# KeeWatch_SAMD21.net
KiCad netlist of a schematic drawn in Altium Designer
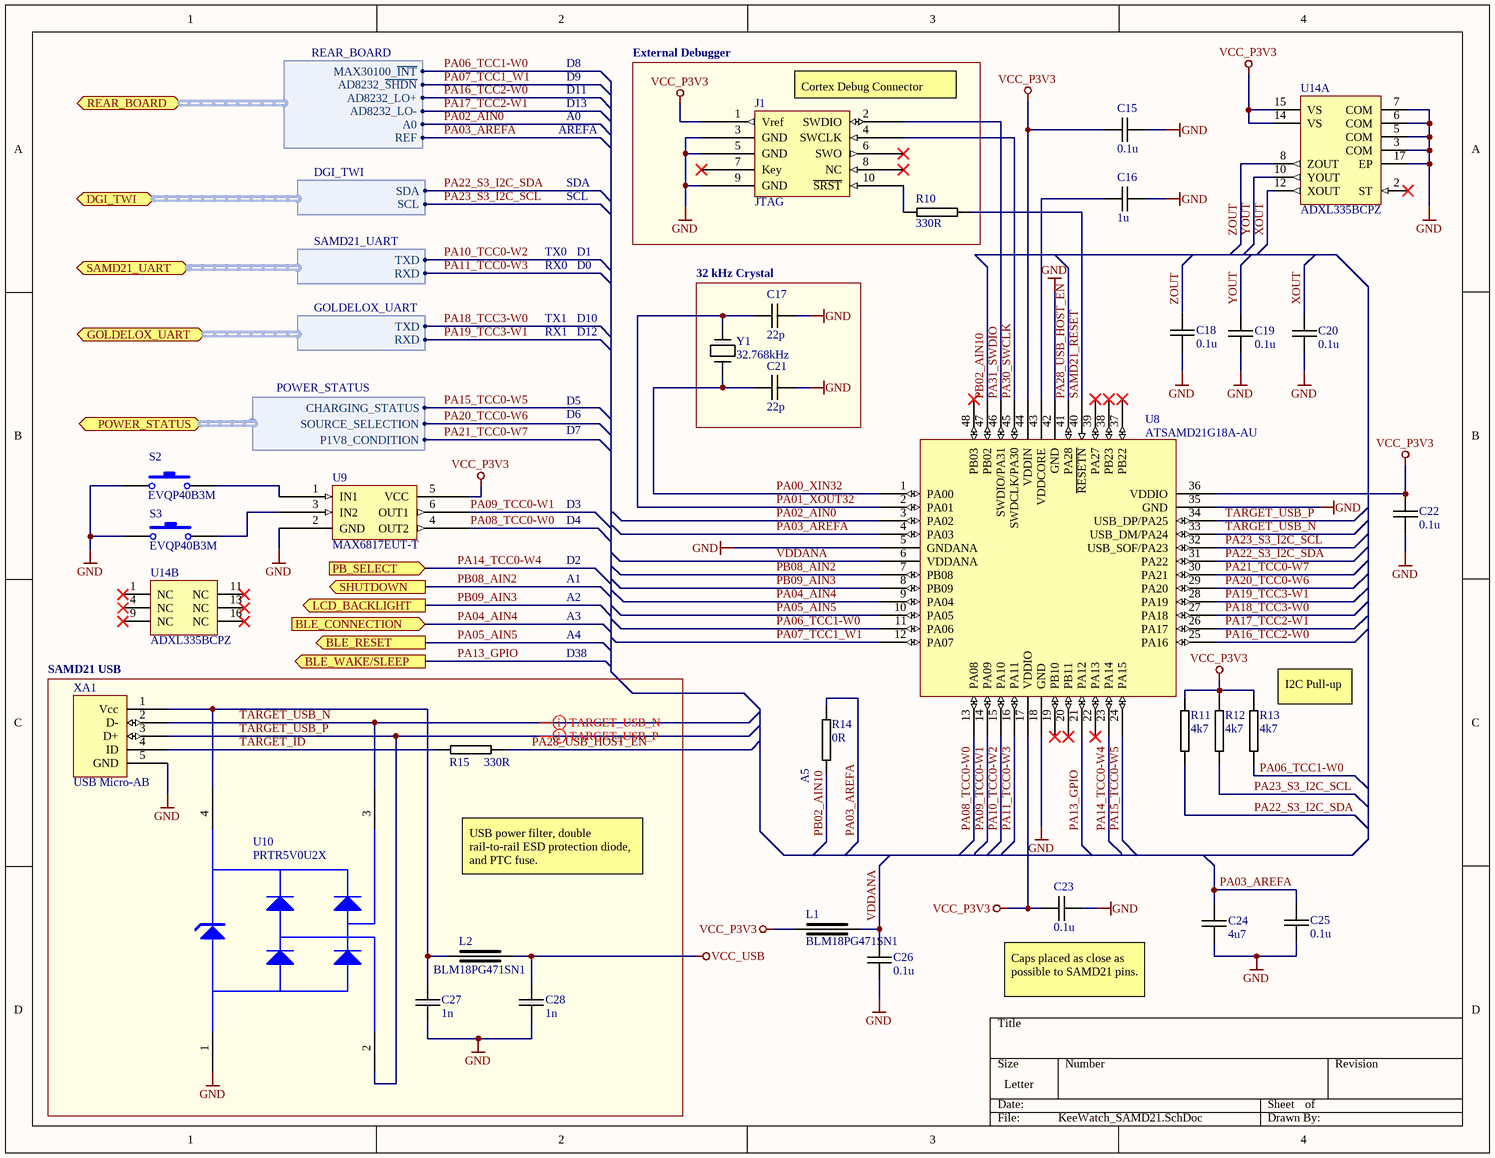
[diagram p0: KeeWatch_SAMD21.SchDoc]

(export (version "E")
  (design (tool "Eeschema 10.0.6"))
  (components
    (comp (ref "C15")
      (value "0.1u")
      (footprint "0603-Cap")
      (description "CAPACITOR 0603 CERAMIC")
      (libsource (lib "Passives") (part "0603-Cap"))
    )
    (comp (ref "C16")
      (value "1u")
      (footprint "0603-Cap")
      (description "CAPACITOR 0603 CERAMIC")
      (libsource (lib "Passives") (part "0603-Cap"))
    )
    (comp (ref "C17")
      (value "22p")
      (footprint "0603-Cap")
      (description "CAPACITOR 0603 CERAMIC")
      (libsource (lib "Passives") (part "0603-Cap"))
    )
    (comp (ref "C18")
      (value "0.1u")
      (footprint "0603-Cap")
      (description "CAPACITOR 0603 CERAMIC")
      (libsource (lib "Passives") (part "0603-Cap"))
    )
    (comp (ref "C19")
      (value "0.1u")
      (footprint "0603-Cap")
      (description "CAPACITOR 0603 CERAMIC")
      (libsource (lib "Passives") (part "0603-Cap"))
    )
    (comp (ref "C20")
      (value "0.1u")
      (footprint "0603-Cap")
      (description "CAPACITOR 0603 CERAMIC")
      (libsource (lib "Passives") (part "0603-Cap"))
    )
    (comp (ref "C21")
      (value "22p")
      (footprint "0603-Cap")
      (description "CAPACITOR 0603 CERAMIC")
      (libsource (lib "Passives") (part "0603-Cap"))
    )
    (comp (ref "C22")
      (value "0.1u")
      (footprint "0603-Cap")
      (description "CAPACITOR 0603 CERAMIC")
      (libsource (lib "Passives") (part "0603-Cap"))
    )
    (comp (ref "C23")
      (value "0.1u")
      (footprint "0603-Cap")
      (description "CAPACITOR 0603 CERAMIC")
      (libsource (lib "Passives") (part "0603-Cap"))
    )
    (comp (ref "C24")
      (value "4u7")
      (footprint "0603-Cap")
      (description "CAPACITOR 0603 CERAMIC")
      (libsource (lib "Passives") (part "0603-Cap"))
    )
    (comp (ref "C25")
      (value "0.1u")
      (footprint "0603-Cap")
      (description "CAPACITOR 0603 CERAMIC")
      (libsource (lib "Passives") (part "0603-Cap"))
    )
    (comp (ref "C26")
      (value "0.1u")
      (footprint "0603-Cap")
      (description "CAPACITOR 0603 CERAMIC")
      (libsource (lib "Passives") (part "0603-Cap"))
    )
    (comp (ref "C27")
      (value "1n")
      (footprint "0603-Cap")
      (description "CAPACITOR 0603 CERAMIC")
      (libsource (lib "Passives") (part "0603-Cap"))
    )
    (comp (ref "C28")
      (value "1n")
      (footprint "0603-Cap")
      (description "CAPACITOR 0603 CERAMIC")
      (libsource (lib "Passives") (part "0603-Cap"))
    )
    (comp (ref "J1")
      (value "JTAG")
      (footprint "SWD CONNECTOR")
      (description "JTAG CONNECTOR")
      (libsource (lib "Schlib2") (part "JTAG"))
    )
    (comp (ref "L1")
      (value "BLM18PG471SN1")
      (footprint "0603-IND")
      (description "FERRITE BEAD 1000 OHM 400mA")
      (fields
        (field (name "MANUFACTURER") "TDK Corporation")
        (field (name "MANUFACTURER PART NUMBER") "MMZ1608R102A")
      )
      (libsource (lib "vh_altium_library") (part "0603FB-1KZ"))
    )
    (comp (ref "L2")
      (value "BLM18PG471SN1")
      (footprint "0603-IND")
      (description "FERRITE BEAD 1000 OHM 400mA")
      (fields
        (field (name "MANUFACTURER") "TDK Corporation")
        (field (name "MANUFACTURER PART NUMBER") "MMZ1608R102A")
      )
      (libsource (lib "vh_altium_library") (part "0603FB-1KZ"))
    )
    (comp (ref "R10")
      (value "330R")
      (footprint "0603-RES")
      (description "GENERIC RESISTOR 0603")
      (libsource (lib "Passives") (part "0603-Res"))
    )
    (comp (ref "R11")
      (value "4k7")
      (footprint "0603-RES")
      (description "GENERIC RESISTOR 0603")
      (libsource (lib "Passives") (part "0603-Res"))
    )
    (comp (ref "R12")
      (value "4k7")
      (footprint "0603-RES")
      (description "GENERIC RESISTOR 0603")
      (libsource (lib "Passives") (part "0603-Res"))
    )
    (comp (ref "R13")
      (value "4k7")
      (footprint "0603-RES")
      (description "GENERIC RESISTOR 0603")
      (libsource (lib "Passives") (part "0603-Res"))
    )
    (comp (ref "R14")
      (value "0R")
      (footprint "0603-RES")
      (description "GENERIC RESISTOR 0603")
      (libsource (lib "Passives") (part "0603-Res"))
    )
    (comp (ref "R15")
      (value "330R")
      (footprint "0603-RES")
      (description "GENERIC RESISTOR 0603")
      (libsource (lib "Passives") (part "0603-Res"))
    )
    (comp (ref "S2") (value "EVQP40B3M") (footprint "EVQP4") (libsource (lib "WATCH") (part "EVQP40B3M")))
    (comp (ref "S3") (value "EVQP40B3M") (footprint "EVQP4") (libsource (lib "WATCH") (part "EVQP40B3M")))
    (comp (ref "U8")
      (value "ATSAMD21G18A-AU")
      (footprint "WATCH:48AA_N")
      (libsource (lib "WATCH") (part "ATSAMD21G18A-AU"))
    )
    (comp (ref "U9")
      (value "MAX6817EUT-T")
      (footprint "WATCH:Z6+1_N")
      (description "±15kV ESD-Protected,Dual, CMOS Switch Debouncer")
      (libsource (lib "Schlib2") (part "MAX6817EUT-T"))
    )
    (comp (ref "U10")
      (value "PRTR5V0U2X")
      (footprint "SOT143B")
      (libsource (lib "WATCH") (part "PRTR5V0U2X"))
    )
    (comp (ref "U14")
      (value "ADXL335BCPZ")
      (footprint "WATCH:ADI-CP-16-14_N")
      (fields (field (name "MANUFACTURER") "Analog Devices"))
      (libsource (lib "") (part "ADXL335BCPZ_1"))
    )
    (comp (ref "XA1")
      (value "USB Micro-AB")
      (footprint "MICRO USB B")
      (description "USB Connectors MICRO USB B RECEPT TOP MOUNT")
      (libsource (lib "WATCH") (part "MICRO USB B"))
    )
    (comp (ref "Y1")
      (value "32.768kHz")
      (footprint "32.768KHZ CRYSTAL")
      (description "32.768kHz SMD LOW PROFILE CRYSTAL")
      (libsource (lib "WATCH") (part "ABS05-32.768KHZ-9-T"))
    )
  )
  (nets
    (net (code "6") (name "/PA00_XIN32") (class "Default")
      (node (ref "C21") (pin "1") (pintype "passive"))
      (node (ref "U8") (pin "1") (pinfunction "PA00_1") (pintype "bidirectional"))
      (node (ref "Y1") (pin "1") (pintype "passive"))
    )
    (net (code "7") (name "/PA01_XOUT32") (class "Default")
      (node (ref "C17") (pin "1") (pintype "passive"))
      (node (ref "U8") (pin "2") (pinfunction "PA01_2") (pintype "bidirectional"))
      (node (ref "Y1") (pin "2") (pintype "passive"))
    )
    (net (code "8") (name "/PA02_AIN0") (class "Default")
      (node (ref "U8") (pin "3") (pinfunction "PA02_3") (pintype "bidirectional"))
    )
    (net (code "9") (name "/PA03_AREFA") (class "Default")
      (node (ref "C24") (pin "2") (pintype "passive"))
      (node (ref "C25") (pin "2") (pintype "passive"))
      (node (ref "R14") (pin "1") (pintype "passive"))
      (node (ref "U8") (pin "4") (pinfunction "PA03_4") (pintype "bidirectional"))
    )
    (net (code "10") (name "/PA04_AIN4") (class "Default")
      (node (ref "U8") (pin "9") (pinfunction "PA04_9") (pintype "bidirectional"))
    )
    (net (code "11") (name "/PA05_AIN5") (class "Default")
      (node (ref "U8") (pin "10") (pinfunction "PA05_10") (pintype "bidirectional"))
    )
    (net (code "12") (name "/PA06_TCC1-W0") (class "Default")
      (node (ref "R13") (pin "2") (pintype "passive"))
      (node (ref "U8") (pin "11") (pinfunction "PA06_11") (pintype "bidirectional"))
    )
    (net (code "13") (name "/PA07_TCC1_W1") (class "Default")
      (node (ref "U8") (pin "12") (pinfunction "PA07_12") (pintype "bidirectional"))
    )
    (net (code "14") (name "/PA08_TCC0-W0") (class "Default")
      (node (ref "U8") (pin "13") (pinfunction "PA08_13") (pintype "bidirectional"))
      (node (ref "U9") (pin "4") (pinfunction "OUT2_4") (pintype "output"))
    )
    (net (code "15") (name "/PA09_TCC0-W1") (class "Default")
      (node (ref "U8") (pin "14") (pinfunction "PA09_14") (pintype "bidirectional"))
      (node (ref "U9") (pin "6") (pinfunction "OUT1_6") (pintype "output"))
    )
    (net (code "16") (name "/PA10_TCC0-W2") (class "Default")
      (node (ref "U8") (pin "15") (pinfunction "PA10_15") (pintype "bidirectional"))
    )
    (net (code "17") (name "/PA11_TCC0-W3") (class "Default")
      (node (ref "U8") (pin "16") (pinfunction "PA11_16") (pintype "bidirectional"))
    )
    (net (code "18") (name "/PA13_GPIO") (class "Default")
      (node (ref "U8") (pin "21") (pinfunction "PA12_21") (pintype "bidirectional"))
    )
    (net (code "19") (name "/PA14_TCC0-W4") (class "Default")
      (node (ref "U8") (pin "23") (pinfunction "PA14_23") (pintype "bidirectional"))
    )
    (net (code "20") (name "/PA15_TCC0-W5") (class "Default")
      (node (ref "U8") (pin "24") (pinfunction "PA15_24") (pintype "bidirectional"))
    )
    (net (code "21") (name "/PA16_TCC2-W0") (class "Default")
      (node (ref "U8") (pin "25") (pinfunction "PA16_25") (pintype "bidirectional"))
    )
    (net (code "22") (name "/PA17_TCC2-W1") (class "Default")
      (node (ref "U8") (pin "26") (pinfunction "PA17_26") (pintype "bidirectional"))
    )
    (net (code "23") (name "/PA18_TCC3-W0") (class "Default")
      (node (ref "U8") (pin "27") (pinfunction "PA18_27") (pintype "bidirectional"))
    )
    (net (code "24") (name "/PA19_TCC3-W1") (class "Default")
      (node (ref "U8") (pin "28") (pinfunction "PA19_28") (pintype "bidirectional"))
    )
    (net (code "25") (name "/PA20_TCC0-W6") (class "Default")
      (node (ref "U8") (pin "29") (pinfunction "PA20_29") (pintype "bidirectional"))
    )
    (net (code "26") (name "/PA21_TCC0-W7") (class "Default")
      (node (ref "U8") (pin "30") (pinfunction "PA21_30") (pintype "bidirectional"))
    )
    (net (code "27") (name "/PA22_S3_I2C_SDA") (class "Default")
      (node (ref "R11") (pin "2") (pintype "passive"))
      (node (ref "U8") (pin "31") (pinfunction "PA22_31") (pintype "bidirectional"))
    )
    (net (code "28") (name "/PA23_S3_I2C_SCL") (class "Default")
      (node (ref "R12") (pin "2") (pintype "passive"))
      (node (ref "U8") (pin "32") (pinfunction "USB_SOF/PA23_32") (pintype "bidirectional"))
    )
    (net (code "29") (name "/PA28_USB_HOST_EN") (class "Default")
      (node (ref "R15") (pin "2") (pintype "passive"))
      (node (ref "U8") (pin "41") (pinfunction "PA28_41") (pintype "bidirectional"))
    )
    (net (code "30") (name "/PA30_SWCLK") (class "Default")
      (node (ref "J1") (pin "4") (pinfunction "SWCLK_4") (pintype "input"))
      (node (ref "U8") (pin "45") (pinfunction "SWDCLK/PA30_45") (pintype "bidirectional"))
    )
    (net (code "31") (name "/PA31_SWDIO") (class "Default")
      (node (ref "J1") (pin "2") (pinfunction "SWDIO_2") (pintype "bidirectional"))
      (node (ref "U8") (pin "46") (pinfunction "SWDIO/PA31_46") (pintype "bidirectional"))
    )
    (net (code "32") (name "/PB02_AIN10") (class "Default")
      (node (ref "R14") (pin "2") (pintype "passive"))
      (node (ref "U8") (pin "47") (pinfunction "PB02_47") (pintype "bidirectional"))
    )
    (net (code "33") (name "/PB08_AIN2") (class "Default")
      (node (ref "U8") (pin "7") (pinfunction "PB08_7") (pintype "bidirectional"))
    )
    (net (code "34") (name "/PB09_AIN3") (class "Default")
      (node (ref "U8") (pin "8") (pinfunction "PB09_8") (pintype "bidirectional"))
    )
    (net (code "35") (name "/SAMD21_RESET") (class "Default")
      (node (ref "R10") (pin "2") (pintype "passive"))
      (node (ref "U8") (pin "40") (pinfunction "~{RESETN}_40") (pintype "input"))
    )
    (net (code "36") (name "/TARGET_ID") (class "Default")
      (node (ref "R15") (pin "1") (pintype "passive"))
      (node (ref "XA1") (pin "4") (pinfunction "ID_4") (pintype "passive"))
    )
    (net (code "37") (name "/TARGET_USB_N") (class "Default")
      (node (ref "U10") (pin "3") (pinfunction "3_3") (pintype "passive"))
      (node (ref "U8") (pin "33") (pinfunction "USB_DM/PA24_33") (pintype "bidirectional"))
      (node (ref "XA1") (pin "2") (pinfunction "D-_2") (pintype "bidirectional"))
    )
    (net (code "38") (name "/TARGET_USB_P") (class "Default")
      (node (ref "U10") (pin "2") (pinfunction "2_2") (pintype "passive"))
      (node (ref "U8") (pin "34") (pinfunction "USB_DP/PA25_34") (pintype "bidirectional"))
      (node (ref "XA1") (pin "3") (pinfunction "D+_3") (pintype "bidirectional"))
    )
    (net (code "39") (name "/VDDANA") (class "Default")
      (node (ref "C26") (pin "1") (pintype "passive"))
      (node (ref "L1") (pin "1") (pintype "passive"))
      (node (ref "U8") (pin "6") (pinfunction "VDDANA_6") (pintype "power_in"))
    )
    (net (code "40") (name "/XOUT") (class "Default")
      (node (ref "C20") (pin "1") (pintype "passive"))
      (node (ref "U14") (pin "12") (pinfunction "XOUT_12") (pintype "output"))
    )
    (net (code "41") (name "/YOUT") (class "Default")
      (node (ref "C19") (pin "1") (pintype "passive"))
      (node (ref "U14") (pin "10") (pinfunction "YOUT_10") (pintype "output"))
    )
    (net (code "42") (name "/ZOUT") (class "Default")
      (node (ref "C18") (pin "2") (pintype "passive"))
      (node (ref "U14") (pin "8") (pinfunction "ZOUT_8") (pintype "output"))
    )
    (net (code "48") (name "GND") (class "Default")
      (node (ref "C15") (pin "2") (pintype "passive"))
      (node (ref "C16") (pin "2") (pintype "passive"))
      (node (ref "C17") (pin "2") (pintype "passive"))
      (node (ref "C18") (pin "1") (pintype "passive"))
      (node (ref "C19") (pin "2") (pintype "passive"))
      (node (ref "C20") (pin "2") (pintype "passive"))
      (node (ref "C21") (pin "2") (pintype "passive"))
      (node (ref "C22") (pin "2") (pintype "passive"))
      (node (ref "C23") (pin "2") (pintype "passive"))
      (node (ref "C24") (pin "1") (pintype "passive"))
      (node (ref "C25") (pin "1") (pintype "passive"))
      (node (ref "C26") (pin "2") (pintype "passive"))
      (node (ref "C27") (pin "2") (pintype "passive"))
      (node (ref "C28") (pin "2") (pintype "passive"))
      (node (ref "J1") (pin "3") (pinfunction "GND_3") (pintype "passive"))
      (node (ref "J1") (pin "5") (pinfunction "GND_5") (pintype "passive"))
      (node (ref "J1") (pin "9") (pinfunction "GND_9") (pintype "passive"))
      (node (ref "S2") (pin "1") (pinfunction "1_1") (pintype "passive"))
      (node (ref "S3") (pin "1") (pinfunction "1_1") (pintype "passive"))
      (node (ref "U10") (pin "1") (pinfunction "1_1") (pintype "passive"))
      (node (ref "U14") (pin "17") (pinfunction "EP_17") (pintype "passive"))
      (node (ref "U14") (pin "3") (pinfunction "COM_3") (pintype "power_in"))
      (node (ref "U14") (pin "5") (pinfunction "COM_5") (pintype "power_in"))
      (node (ref "U14") (pin "6") (pinfunction "COM_6") (pintype "power_in"))
      (node (ref "U14") (pin "7") (pinfunction "COM_7") (pintype "power_in"))
      (node (ref "U8") (pin "18") (pinfunction "GND_18") (pintype "passive"))
      (node (ref "U8") (pin "35") (pinfunction "GND_35") (pintype "passive"))
      (node (ref "U8") (pin "42") (pinfunction "GND_42") (pintype "passive"))
      (node (ref "U8") (pin "5") (pinfunction "GNDANA_5") (pintype "passive"))
      (node (ref "U9") (pin "2") (pinfunction "GND_2") (pintype "passive"))
      (node (ref "XA1") (pin "5") (pinfunction "GND_5") (pintype "passive"))
    )
    (net (code "49") (name "Net-(J1-~{SRST})") (class "Default")
      (node (ref "J1") (pin "10") (pinfunction "~{SRST}_10") (pintype "input"))
      (node (ref "R10") (pin "1") (pintype "passive"))
    )
    (net (code "50") (name "Net-(U8-VDDCORE)") (class "Default")
      (node (ref "C16") (pin "1") (pintype "passive"))
      (node (ref "U8") (pin "43") (pinfunction "VDDCORE_43") (pintype "power_in"))
    )
    (net (code "51") (name "Net-(U9-IN1)") (class "Default")
      (node (ref "S2") (pin "2") (pinfunction "2_2") (pintype "passive"))
      (node (ref "U9") (pin "1") (pinfunction "IN1_1") (pintype "input"))
    )
    (net (code "52") (name "Net-(U9-IN2)") (class "Default")
      (node (ref "S3") (pin "2") (pinfunction "2_2") (pintype "passive"))
      (node (ref "U9") (pin "3") (pinfunction "IN2_3") (pintype "input"))
    )
    (net (code "53") (name "Net-(XA1-Vcc)") (class "Default")
      (node (ref "C27") (pin "1") (pintype "passive"))
      (node (ref "L2") (pin "2") (pintype "passive"))
      (node (ref "U10") (pin "4") (pinfunction "4_4") (pintype "passive"))
      (node (ref "XA1") (pin "1") (pinfunction "Vcc_1") (pintype "power_in"))
    )
    (net (code "54") (name "VCC_P3V3") (class "Default")
      (node (ref "C15") (pin "1") (pintype "passive"))
      (node (ref "C22") (pin "1") (pintype "passive"))
      (node (ref "C23") (pin "1") (pintype "passive"))
      (node (ref "J1") (pin "1") (pinfunction "Vref_1") (pintype "output"))
      (node (ref "L1") (pin "2") (pintype "passive"))
      (node (ref "R11") (pin "1") (pintype "passive"))
      (node (ref "R12") (pin "1") (pintype "passive"))
      (node (ref "R13") (pin "1") (pintype "passive"))
      (node (ref "U14") (pin "14") (pinfunction "VS_14") (pintype "power_in"))
      (node (ref "U14") (pin "15") (pinfunction "VS_15") (pintype "power_in"))
      (node (ref "U8") (pin "17") (pinfunction "VDDIO_17") (pintype "power_in"))
      (node (ref "U8") (pin "36") (pinfunction "VDDIO_36") (pintype "power_in"))
      (node (ref "U8") (pin "44") (pinfunction "VDDIN_44") (pintype "power_in"))
      (node (ref "U9") (pin "5") (pinfunction "VCC_5") (pintype "power_in"))
    )
    (net (code "55") (name "VCC_USB") (class "Default")
      (node (ref "C28") (pin "1") (pintype "passive"))
      (node (ref "L2") (pin "1") (pintype "passive"))
    )
    (net (code "56") (name "unconnected-(J1-Key-Pad7)") (class "Default")
      (node (ref "J1") (pin "7") (pinfunction "Key_7") (pintype "passive+no_connect"))
    )
    (net (code "57") (name "unconnected-(J1-NC-Pad8)") (class "Default")
      (node (ref "J1") (pin "8") (pinfunction "NC_8") (pintype "input+no_connect"))
    )
    (net (code "58") (name "unconnected-(J1-SWO-Pad6)") (class "Default")
      (node (ref "J1") (pin "6") (pinfunction "SWO_6") (pintype "output+no_connect"))
    )
    (net (code "59") (name "unconnected-(U8-PA13-Pad22)") (class "Default")
      (node (ref "U8") (pin "22") (pinfunction "PA13_22") (pintype "bidirectional+no_connect"))
    )
    (net (code "60") (name "unconnected-(U8-PA27-Pad39)") (class "Default")
      (node (ref "U8") (pin "39") (pinfunction "PA27_39") (pintype "bidirectional+no_connect"))
    )
    (net (code "61") (name "unconnected-(U8-PB03-Pad48)") (class "Default")
      (node (ref "U8") (pin "48") (pinfunction "PB03_48") (pintype "bidirectional+no_connect"))
    )
    (net (code "62") (name "unconnected-(U8-PB10-Pad19)") (class "Default")
      (node (ref "U8") (pin "19") (pinfunction "PB10_19") (pintype "bidirectional+no_connect"))
    )
    (net (code "63") (name "unconnected-(U8-PB11-Pad20)") (class "Default")
      (node (ref "U8") (pin "20") (pinfunction "PB11_20") (pintype "bidirectional+no_connect"))
    )
    (net (code "64") (name "unconnected-(U8-PB22-Pad37)") (class "Default")
      (node (ref "U8") (pin "37") (pinfunction "PB22_37") (pintype "bidirectional+no_connect"))
    )
    (net (code "65") (name "unconnected-(U8-PB23-Pad38)") (class "Default")
      (node (ref "U8") (pin "38") (pinfunction "PB23_38") (pintype "bidirectional+no_connect"))
    )
    (net (code "66") (name "unconnected-(U14A-ST-Pad2)") (class "Default")
      (node (ref "U14") (pin "2") (pinfunction "ST_2") (pintype "input+no_connect"))
    )
    (net (code "67") (name "unconnected-(U14B-NC-Pad1)") (class "Default")
      (node (ref "U14") (pin "1") (pinfunction "NC_1") (pintype "passive+no_connect"))
    )
    (net (code "68") (name "unconnected-(U14B-NC-Pad4)") (class "Default")
      (node (ref "U14") (pin "4") (pinfunction "NC_4") (pintype "passive+no_connect"))
    )
    (net (code "69") (name "unconnected-(U14B-NC-Pad9)") (class "Default")
      (node (ref "U14") (pin "9") (pinfunction "NC_9") (pintype "passive+no_connect"))
    )
    (net (code "70") (name "unconnected-(U14B-NC-Pad11)") (class "Default")
      (node (ref "U14") (pin "11") (pinfunction "NC_11") (pintype "passive+no_connect"))
    )
    (net (code "71") (name "unconnected-(U14B-NC-Pad13)") (class "Default")
      (node (ref "U14") (pin "13") (pinfunction "NC_13") (pintype "passive+no_connect"))
    )
    (net (code "72") (name "unconnected-(U14B-NC-Pad16)") (class "Default")
      (node (ref "U14") (pin "16") (pinfunction "NC_16") (pintype "passive+no_connect"))
    )
  )
)
